# shemat.net
KiCad netlist of a schematic drawn in Altium Designer
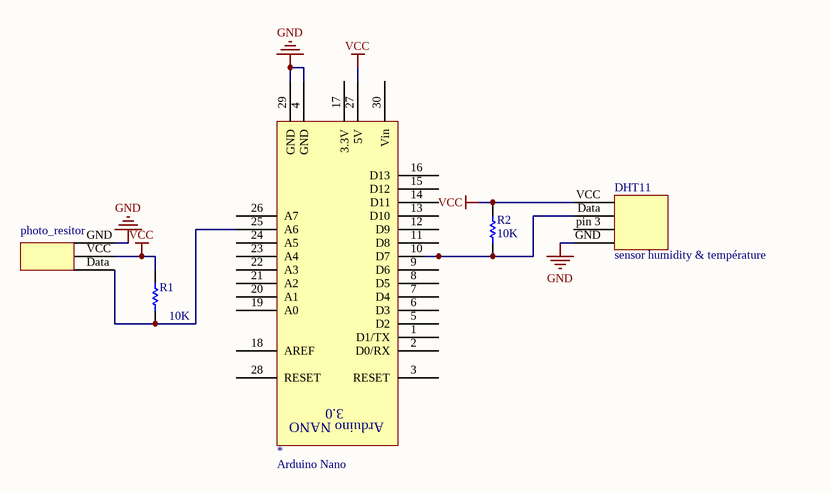
[diagram p0: shemat.SchDoc]

(export (version "E")
  (design (tool "Eeschema 10.0.6"))
  (components
    (comp (ref "*")
      (value "Arduino Nano")
      (footprint "Arduino Nano FootPrint")
      (libsource (lib "Integrated_Library") (part "Arduino Nano"))
    )
    (comp (ref "DHT11")
      (value "sensor humidity & température")
      (footprint "DHT11")
      (libsource (lib "sensors") (part "DHT11"))
    )
    (comp (ref "photo_resitor")
      (value "~")
      (footprint "photo_resitor")
      (libsource (lib "sensors") (part "photo_resistor"))
    )
    (comp (ref "R1")
      (value "10K")
      (footprint "AXIAL-0.3")
      (description "Resistor")
      (fields (field (name "Comment") "Res1") (field (name "PUBLISHER") "Altium Limited"))
      (libsource (lib "Miscellaneous Devices") (part "Res1"))
    )
    (comp (ref "R2")
      (value "10K")
      (footprint "AXIAL-0.3")
      (description "Resistor")
      (fields (field (name "Comment") "Res1") (field (name "PUBLISHER") "Altium Limited"))
      (libsource (lib "Miscellaneous Devices") (part "Res1"))
    )
  )
  (nets
    (net (code "1") (name "GND") (class "Default")
      (node (ref "*") (pin "29") (pinfunction "GND_29") (pintype "passive"))
      (node (ref "*") (pin "4") (pinfunction "GND_4") (pintype "passive"))
      (node (ref "DHT11") (pin "GND") (pinfunction "GND_GND") (pintype "passive"))
      (node (ref "photo_resitor") (pin "GND") (pinfunction "gnd_GND") (pintype "passive"))
    )
    (net (code "2") (name "Net-(*-A6)") (class "Default")
      (node (ref "*") (pin "25") (pinfunction "A6_25") (pintype "passive"))
      (node (ref "R1") (pin "2") (pinfunction "2_2") (pintype "passive"))
      (node (ref "photo_resitor") (pin "Data") (pinfunction "data_Data") (pintype "passive"))
    )
    (net (code "3") (name "Net-(*-D7)") (class "Default")
      (node (ref "*") (pin "10") (pinfunction "D7_10") (pintype "passive"))
      (node (ref "DHT11") (pin "Data") (pinfunction "data_Data") (pintype "passive"))
      (node (ref "R2") (pin "1") (pinfunction "1_1") (pintype "passive"))
    )
    (net (code "4") (name "VCC") (class "Default")
      (node (ref "*") (pin "27") (pinfunction "5V_27") (pintype "passive"))
      (node (ref "DHT11") (pin "VCC") (pinfunction "vcc_VCC") (pintype "passive"))
      (node (ref "R1") (pin "1") (pinfunction "1_1") (pintype "passive"))
      (node (ref "R2") (pin "2") (pinfunction "2_2") (pintype "passive"))
      (node (ref "photo_resitor") (pin "VCC") (pinfunction "data_VCC") (pintype "passive"))
    )
    (net (code "5") (name "unconnected-(*-3.3V-Pad17)") (class "Default")
      (node (ref "*") (pin "17") (pinfunction "3.3V_17") (pintype "passive"))
    )
    (net (code "6") (name "unconnected-(*-A0-Pad19)") (class "Default")
      (node (ref "*") (pin "19") (pinfunction "A0_19") (pintype "passive"))
    )
    (net (code "7") (name "unconnected-(*-A1-Pad20)") (class "Default")
      (node (ref "*") (pin "20") (pinfunction "A1_20") (pintype "passive"))
    )
    (net (code "8") (name "unconnected-(*-A2-Pad21)") (class "Default")
      (node (ref "*") (pin "21") (pinfunction "A2_21") (pintype "passive"))
    )
    (net (code "9") (name "unconnected-(*-A3-Pad22)") (class "Default")
      (node (ref "*") (pin "22") (pinfunction "A3_22") (pintype "passive"))
    )
    (net (code "10") (name "unconnected-(*-A4-Pad23)") (class "Default")
      (node (ref "*") (pin "23") (pinfunction "A4_23") (pintype "passive"))
    )
    (net (code "11") (name "unconnected-(*-A5-Pad24)") (class "Default")
      (node (ref "*") (pin "24") (pinfunction "A5_24") (pintype "passive"))
    )
    (net (code "12") (name "unconnected-(*-A7-Pad26)") (class "Default")
      (node (ref "*") (pin "26") (pinfunction "A7_26") (pintype "passive"))
    )
    (net (code "13") (name "unconnected-(*-AREF-Pad18)") (class "Default")
      (node (ref "*") (pin "18") (pinfunction "AREF_18") (pintype "passive"))
    )
    (net (code "14") (name "unconnected-(*-D0{slash}RX-Pad2)") (class "Default")
      (node (ref "*") (pin "2") (pinfunction "D0/RX_2") (pintype "passive"))
    )
    (net (code "15") (name "unconnected-(*-D1{slash}TX-Pad1)") (class "Default")
      (node (ref "*") (pin "1") (pinfunction "D1/TX_1") (pintype "passive"))
    )
    (net (code "16") (name "unconnected-(*-D2-Pad5)") (class "Default")
      (node (ref "*") (pin "5") (pinfunction "D2_5") (pintype "passive"))
    )
    (net (code "17") (name "unconnected-(*-D3-Pad6)") (class "Default")
      (node (ref "*") (pin "6") (pinfunction "D3_6") (pintype "passive"))
    )
    (net (code "18") (name "unconnected-(*-D4-Pad7)") (class "Default")
      (node (ref "*") (pin "7") (pinfunction "D4_7") (pintype "passive"))
    )
    (net (code "19") (name "unconnected-(*-D5-Pad8)") (class "Default")
      (node (ref "*") (pin "8") (pinfunction "D5_8") (pintype "passive"))
    )
    (net (code "20") (name "unconnected-(*-D6-Pad9)") (class "Default")
      (node (ref "*") (pin "9") (pinfunction "D6_9") (pintype "passive"))
    )
    (net (code "21") (name "unconnected-(*-D8-Pad11)") (class "Default")
      (node (ref "*") (pin "11") (pinfunction "D8_11") (pintype "passive"))
    )
    (net (code "22") (name "unconnected-(*-D9-Pad12)") (class "Default")
      (node (ref "*") (pin "12") (pinfunction "D9_12") (pintype "passive"))
    )
    (net (code "23") (name "unconnected-(*-D10-Pad13)") (class "Default")
      (node (ref "*") (pin "13") (pinfunction "D10_13") (pintype "passive"))
    )
    (net (code "24") (name "unconnected-(*-D11-Pad14)") (class "Default")
      (node (ref "*") (pin "14") (pinfunction "D11_14") (pintype "passive"))
    )
    (net (code "25") (name "unconnected-(*-D12-Pad15)") (class "Default")
      (node (ref "*") (pin "15") (pinfunction "D12_15") (pintype "passive"))
    )
    (net (code "26") (name "unconnected-(*-D13-Pad16)") (class "Default")
      (node (ref "*") (pin "16") (pinfunction "D13_16") (pintype "passive"))
    )
    (net (code "27") (name "unconnected-(*-RESET-Pad3)") (class "Default")
      (node (ref "*") (pin "3") (pinfunction "RESET_3") (pintype "passive"))
    )
    (net (code "28") (name "unconnected-(*-RESET-Pad28)") (class "Default")
      (node (ref "*") (pin "28") (pinfunction "RESET_28") (pintype "passive"))
    )
    (net (code "29") (name "unconnected-(*-Vin-Pad30)") (class "Default")
      (node (ref "*") (pin "30") (pinfunction "Vin_30") (pintype "passive"))
    )
    (net (code "30") (name "unconnected-(DHT11-4-Padpin_3)") (class "Default")
      (node (ref "DHT11") (pin "pin_3") (pinfunction "4_pin_3") (pintype "passive"))
    )
  )
)
